# atmel.net
KiCad netlist of a schematic drawn in Altium Designer
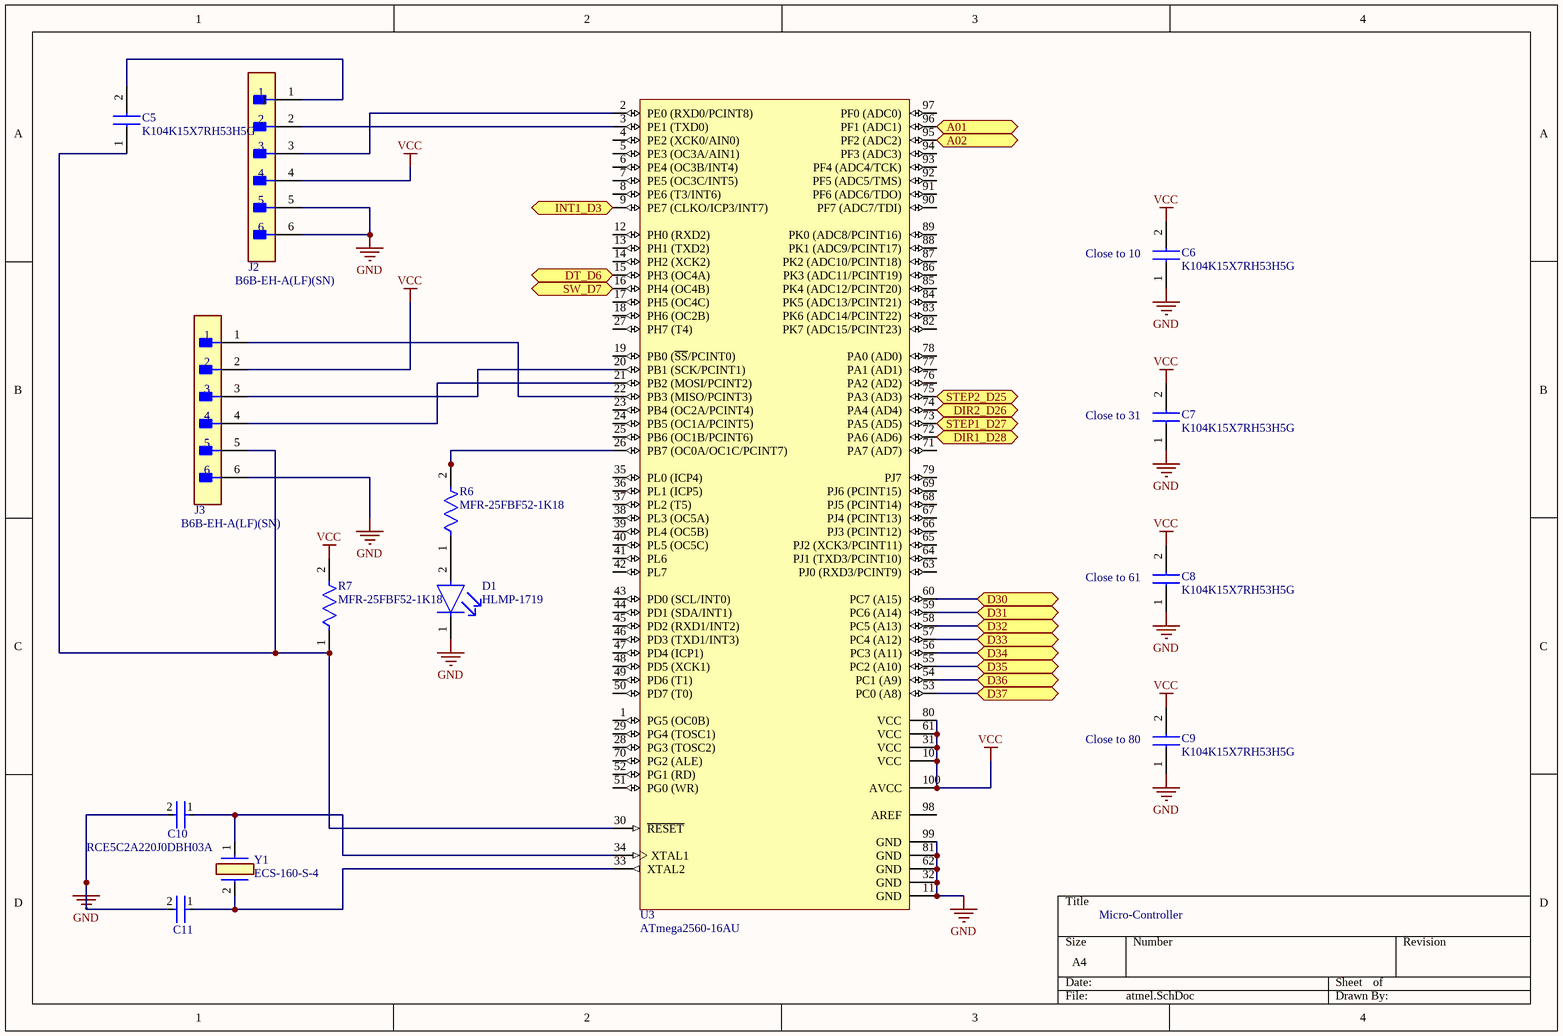
[diagram p0: atmel.SchDoc]

(export (version "E")
  (design (tool "Eeschema 10.0.6"))
  (components
    (comp (ref "C5")
      (value "K104K15X7RH53H5G")
      (footprint "SamacSys:K104K15X7RH53H5G")
      (description "Capacitor")
      (fields (field (name "MOUSER PART NUMBER") "594-K104K15X7RH53H5G"))
      (libsource (lib "*") (part "K104K15X7RH53H5G"))
    )
    (comp (ref "C6")
      (value "K104K15X7RH53H5G")
      (footprint "SamacSys:K104K15X7RH53H5G")
      (description "Capacitor")
      (fields (field (name "MOUSER PART NUMBER") "594-K104K15X7RH53H5G"))
      (libsource (lib "*") (part "K104K15X7RH53H5G"))
    )
    (comp (ref "C7")
      (value "K104K15X7RH53H5G")
      (footprint "SamacSys:K104K15X7RH53H5G")
      (description "Capacitor")
      (fields (field (name "MOUSER PART NUMBER") "594-K104K15X7RH53H5G"))
      (libsource (lib "*") (part "K104K15X7RH53H5G"))
    )
    (comp (ref "C8")
      (value "K104K15X7RH53H5G")
      (footprint "SamacSys:K104K15X7RH53H5G")
      (description "Capacitor")
      (fields (field (name "MOUSER PART NUMBER") "594-K104K15X7RH53H5G"))
      (libsource (lib "*") (part "K104K15X7RH53H5G"))
    )
    (comp (ref "C9")
      (value "K104K15X7RH53H5G")
      (footprint "SamacSys:K104K15X7RH53H5G")
      (description "Capacitor")
      (fields (field (name "MOUSER PART NUMBER") "594-K104K15X7RH53H5G"))
      (libsource (lib "*") (part "K104K15X7RH53H5G"))
    )
    (comp (ref "C10")
      (value "RCE5C2A220J0DBH03A")
      (footprint "FP-RCE0DB-MFG")
      (description "Cap Ceramic 22pF 100V C0G ±5% Radial 2.5mm +125°C Ammo Pack")
      (fields (field (name "VOLTAGE") "100V") (field (name "TOLERANCE") "5%"))
      (libsource (lib "Altium Content Vault") (part "b4654b650e69147ec39a6b967a45e02"))
    )
    (comp (ref "C11")
      (value "RCE5C2A220J0DBH03A")
      (footprint "FP-RCE0DB-MFG")
      (description "Cap Ceramic 22pF 100V C0G ±5% Radial 2.5mm +125°C Ammo Pack")
      (fields (field (name "VOLTAGE") "100V") (field (name "TOLERANCE") "5%"))
      (libsource (lib "Altium Content Vault") (part "b4654b650e69147ec39a6b967a45e02"))
    )
    (comp (ref "D1")
      (value "HLMP-1719")
      (footprint "FP-HLMP-1719-MFG")
      (description "LED YELLOW DIFFUSED T-1 T/H")
      (fields
        (field (name "MANUFACTURER") "Broadcom")
        (field (name "OCTOPART") "https://octopart.com/hlmp-1719-broadcom-71130405")
      )
      (libsource (lib "Altium Content Vault") (part "8706943c75ba83719d021d2fdc84c58"))
    )
    (comp (ref "J2")
      (value "B6B-EH-A(LF)(SN)")
      (footprint "FP-B6B-EH-A_LF_SN-MFG")
      (description "CONN HEADER VERT 6POS 2.5MM")
      (libsource (lib "") (part "f2cb566baf1c37ab5a3b8e90bbeafd6_1"))
    )
    (comp (ref "J3")
      (value "B6B-EH-A(LF)(SN)")
      (footprint "FP-B6B-EH-A_LF_SN-MFG")
      (description "CONN HEADER VERT 6POS 2.5MM")
      (libsource (lib "Altium Content Vault") (part "f2cb566baf1c37ab5a3b8e90bbeafd6"))
    )
    (comp (ref "R6")
      (value "MFR-25FBF52-1K18")
      (footprint "FP-MFR-25-MFG")
      (description "RES 1.18K OHM 1/4W 1% AXIAL")
      (fields (field (name "MANUFACTURER") "Yageo") (field (name "TOLERANCE") "1%"))
      (libsource (lib "Altium Content Vault") (part "1029c3af85768c4190bb7ad29bc67b5"))
    )
    (comp (ref "R7")
      (value "MFR-25FBF52-1K18")
      (footprint "FP-MFR-25-MFG")
      (description "RES 1.18K OHM 1/4W 1% AXIAL")
      (fields (field (name "MANUFACTURER") "Yageo") (field (name "TOLERANCE") "1%"))
      (libsource (lib "Altium Content Vault") (part "1029c3af85768c4190bb7ad29bc67b5"))
    )
    (comp (ref "U3")
      (value "ATmega2560-16AU")
      (footprint "100A_M")
      (libsource (lib "Altium Content Vault") (part "MC-8B-ATM640-SQ100"))
    )
    (comp (ref "Y1")
      (value "ECS-160-S-4")
      (footprint "SamacSys:ECS160S4")
      (description "Crystal or Oscillator")
      (fields (field (name "MOUSER PART NUMBER") "520-HCU1600-S"))
      (libsource (lib "*") (part "ECS-160-S-4"))
    )
  )
  (nets
    (net (code "1") (name "/A01") (class "Default")
      (node (ref "U3") (pin "96") (pinfunction "PF1_(ADC1)_96") (pintype "bidirectional"))
    )
    (net (code "2") (name "/A02") (class "Default")
      (node (ref "U3") (pin "95") (pinfunction "PF2_(ADC2)_95") (pintype "bidirectional"))
    )
    (net (code "3") (name "/D30") (class "Default")
      (node (ref "U3") (pin "60") (pinfunction "PC7_(A15)_60") (pintype "bidirectional"))
    )
    (net (code "4") (name "/D31") (class "Default")
      (node (ref "U3") (pin "59") (pinfunction "PC6_(A14)_59") (pintype "bidirectional"))
    )
    (net (code "5") (name "/D32") (class "Default")
      (node (ref "U3") (pin "58") (pinfunction "PC5_(A13)_58") (pintype "bidirectional"))
    )
    (net (code "6") (name "/D33") (class "Default")
      (node (ref "U3") (pin "57") (pinfunction "PC4_(A12)_57") (pintype "bidirectional"))
    )
    (net (code "7") (name "/D34") (class "Default")
      (node (ref "U3") (pin "56") (pinfunction "PC3_(A11)_56") (pintype "bidirectional"))
    )
    (net (code "8") (name "/D35") (class "Default")
      (node (ref "U3") (pin "55") (pinfunction "PC2_(A10)_55") (pintype "bidirectional"))
    )
    (net (code "9") (name "/D36") (class "Default")
      (node (ref "U3") (pin "54") (pinfunction "PC1_(A9)_54") (pintype "bidirectional"))
    )
    (net (code "10") (name "/D37") (class "Default")
      (node (ref "U3") (pin "53") (pinfunction "PC0_(A8)_53") (pintype "bidirectional"))
    )
    (net (code "11") (name "/DIR1_D28") (class "Default")
      (node (ref "U3") (pin "72") (pinfunction "PA6_(AD6)_72") (pintype "bidirectional"))
    )
    (net (code "12") (name "/DIR2_D26") (class "Default")
      (node (ref "U3") (pin "74") (pinfunction "PA4_(AD4)_74") (pintype "bidirectional"))
    )
    (net (code "13") (name "/DT_D6") (class "Default")
      (node (ref "U3") (pin "15") (pinfunction "PH3_(OC4A)_15") (pintype "bidirectional"))
    )
    (net (code "14") (name "/INT1_D3") (class "Default")
      (node (ref "U3") (pin "9") (pinfunction "PE7_(CLKO/ICP3/INT7)_9") (pintype "bidirectional"))
    )
    (net (code "15") (name "/STEP1_D27") (class "Default")
      (node (ref "U3") (pin "73") (pinfunction "PA5_(AD5)_73") (pintype "bidirectional"))
    )
    (net (code "16") (name "/STEP2_D25") (class "Default")
      (node (ref "U3") (pin "75") (pinfunction "PA3_(AD3)_75") (pintype "bidirectional"))
    )
    (net (code "17") (name "/SW_D7") (class "Default")
      (node (ref "U3") (pin "16") (pinfunction "PH4_(OC4B)_16") (pintype "bidirectional"))
    )
    (net (code "18") (name "GND") (class "Default")
      (node (ref "C10") (pin "2") (pinfunction "2_2") (pintype "passive"))
      (node (ref "C11") (pin "2") (pinfunction "2_2") (pintype "passive"))
      (node (ref "C6") (pin "1") (pinfunction "1_1") (pintype "passive"))
      (node (ref "C7") (pin "1") (pinfunction "1_1") (pintype "passive"))
      (node (ref "C8") (pin "1") (pinfunction "1_1") (pintype "passive"))
      (node (ref "C9") (pin "1") (pinfunction "1_1") (pintype "passive"))
      (node (ref "D1") (pin "1") (pinfunction "C_1") (pintype "passive"))
      (node (ref "J2") (pin "5") (pinfunction "5_5") (pintype "passive"))
      (node (ref "J2") (pin "6") (pinfunction "6_6") (pintype "passive"))
      (node (ref "J3") (pin "6") (pinfunction "6_6") (pintype "passive"))
      (node (ref "U3") (pin "11") (pinfunction "GND_11") (pintype "power_in"))
      (node (ref "U3") (pin "32") (pinfunction "GND_32") (pintype "power_in"))
      (node (ref "U3") (pin "62") (pinfunction "GND_62") (pintype "power_in"))
      (node (ref "U3") (pin "81") (pinfunction "GND_81") (pintype "power_in"))
      (node (ref "U3") (pin "99") (pinfunction "GND_99") (pintype "power_in"))
    )
    (net (code "19") (name "Net-(C5-Pad2)") (class "Default")
      (node (ref "C5") (pin "2") (pinfunction "2_2") (pintype "passive"))
      (node (ref "J2") (pin "1") (pinfunction "1_1") (pintype "passive"))
    )
    (net (code "20") (name "Net-(D1-A)") (class "Default")
      (node (ref "D1") (pin "2") (pinfunction "A_2") (pintype "passive"))
      (node (ref "R6") (pin "1") (pinfunction "1_1") (pintype "passive"))
    )
    (net (code "21") (name "Net-(U3-PB1_(SCK{slash}PCINT1))") (class "Default")
      (node (ref "J3") (pin "3") (pinfunction "3_3") (pintype "passive"))
      (node (ref "U3") (pin "20") (pinfunction "PB1_(SCK/PCINT1)_20") (pintype "bidirectional"))
    )
    (net (code "22") (name "Net-(U3-PB2_(MOSI{slash}PCINT2))") (class "Default")
      (node (ref "J3") (pin "4") (pinfunction "4_4") (pintype "passive"))
      (node (ref "U3") (pin "21") (pinfunction "PB2_(MOSI/PCINT2)_21") (pintype "bidirectional"))
    )
    (net (code "23") (name "Net-(U3-PB3_(MISO{slash}PCINT3))") (class "Default")
      (node (ref "J3") (pin "1") (pinfunction "1_1") (pintype "passive"))
      (node (ref "U3") (pin "22") (pinfunction "PB3_(MISO/PCINT3)_22") (pintype "bidirectional"))
    )
    (net (code "24") (name "Net-(U3-PB7_(OC0A{slash}OC1C{slash}PCINT7))") (class "Default")
      (node (ref "R6") (pin "2") (pinfunction "2_2") (pintype "passive"))
      (node (ref "U3") (pin "26") (pinfunction "PB7_(OC0A/OC1C/PCINT7)_26") (pintype "bidirectional"))
    )
    (net (code "25") (name "Net-(U3-PE0_(RXD0{slash}PCINT8))") (class "Default")
      (node (ref "J2") (pin "3") (pinfunction "3_3") (pintype "passive"))
      (node (ref "U3") (pin "2") (pinfunction "PE0_(RXD0/PCINT8)_2") (pintype "bidirectional"))
    )
    (net (code "26") (name "Net-(U3-PE1_(TXD0))") (class "Default")
      (node (ref "J2") (pin "2") (pinfunction "2_2") (pintype "passive"))
      (node (ref "U3") (pin "3") (pinfunction "PE1_(TXD0)_3") (pintype "bidirectional"))
    )
    (net (code "27") (name "Net-(U3-XTAL1)") (class "Default")
      (node (ref "C10") (pin "1") (pinfunction "1_1") (pintype "passive"))
      (node (ref "U3") (pin "34") (pinfunction "XTAL1_34") (pintype "input"))
      (node (ref "Y1") (pin "1") (pinfunction "1_1") (pintype "passive"))
    )
    (net (code "28") (name "Net-(U3-XTAL2)") (class "Default")
      (node (ref "C11") (pin "1") (pinfunction "1_1") (pintype "passive"))
      (node (ref "U3") (pin "33") (pinfunction "XTAL2_33") (pintype "output"))
      (node (ref "Y1") (pin "2") (pinfunction "2_2") (pintype "passive"))
    )
    (net (code "29") (name "Net-(U3-~{RESET})") (class "Default")
      (node (ref "C5") (pin "1") (pinfunction "1_1") (pintype "passive"))
      (node (ref "J3") (pin "5") (pinfunction "5_5") (pintype "passive"))
      (node (ref "R7") (pin "1") (pinfunction "1_1") (pintype "passive"))
      (node (ref "U3") (pin "30") (pinfunction "~{RESET}_30") (pintype "input"))
    )
    (net (code "30") (name "VCC") (class "Default")
      (node (ref "C6") (pin "2") (pinfunction "2_2") (pintype "passive"))
      (node (ref "C7") (pin "2") (pinfunction "2_2") (pintype "passive"))
      (node (ref "C8") (pin "2") (pinfunction "2_2") (pintype "passive"))
      (node (ref "C9") (pin "2") (pinfunction "2_2") (pintype "passive"))
      (node (ref "J2") (pin "4") (pinfunction "4_4") (pintype "passive"))
      (node (ref "J3") (pin "2") (pinfunction "2_2") (pintype "passive"))
      (node (ref "R7") (pin "2") (pinfunction "2_2") (pintype "passive"))
      (node (ref "U3") (pin "10") (pinfunction "VCC_10") (pintype "power_in"))
      (node (ref "U3") (pin "100") (pinfunction "AVCC_100") (pintype "power_in"))
      (node (ref "U3") (pin "31") (pinfunction "VCC_31") (pintype "power_in"))
      (node (ref "U3") (pin "61") (pinfunction "VCC_61") (pintype "power_in"))
      (node (ref "U3") (pin "80") (pinfunction "VCC_80") (pintype "power_in"))
    )
    (net (code "31") (name "unconnected-(U3-AREF-Pad98)") (class "Default")
      (node (ref "U3") (pin "98") (pinfunction "AREF_98") (pintype "power_in"))
    )
    (net (code "32") (name "unconnected-(U3-PA0_(AD0)-Pad78)") (class "Default")
      (node (ref "U3") (pin "78") (pinfunction "PA0_(AD0)_78") (pintype "bidirectional"))
    )
    (net (code "33") (name "unconnected-(U3-PA1_(AD1)-Pad77)") (class "Default")
      (node (ref "U3") (pin "77") (pinfunction "PA1_(AD1)_77") (pintype "bidirectional"))
    )
    (net (code "34") (name "unconnected-(U3-PA2_(AD2)-Pad76)") (class "Default")
      (node (ref "U3") (pin "76") (pinfunction "PA2_(AD2)_76") (pintype "bidirectional"))
    )
    (net (code "35") (name "unconnected-(U3-PA7_(AD7)-Pad71)") (class "Default")
      (node (ref "U3") (pin "71") (pinfunction "PA7_(AD7)_71") (pintype "bidirectional"))
    )
    (net (code "36") (name "unconnected-(U3-PB0_(~{SS}{slash}PCINT0)-Pad19)") (class "Default")
      (node (ref "U3") (pin "19") (pinfunction "PB0_(~{SS}/PCINT0)_19") (pintype "bidirectional"))
    )
    (net (code "37") (name "unconnected-(U3-PB4_(OC2A{slash}PCINT4)-Pad23)") (class "Default")
      (node (ref "U3") (pin "23") (pinfunction "PB4_(OC2A/PCINT4)_23") (pintype "bidirectional"))
    )
    (net (code "38") (name "unconnected-(U3-PB5_(OC1A{slash}PCINT5)-Pad24)") (class "Default")
      (node (ref "U3") (pin "24") (pinfunction "PB5_(OC1A/PCINT5)_24") (pintype "bidirectional"))
    )
    (net (code "39") (name "unconnected-(U3-PB6_(OC1B{slash}PCINT6)-Pad25)") (class "Default")
      (node (ref "U3") (pin "25") (pinfunction "PB6_(OC1B/PCINT6)_25") (pintype "bidirectional"))
    )
    (net (code "40") (name "unconnected-(U3-PD0_(SCL{slash}INT0)-Pad43)") (class "Default")
      (node (ref "U3") (pin "43") (pinfunction "PD0_(SCL/INT0)_43") (pintype "bidirectional"))
    )
    (net (code "41") (name "unconnected-(U3-PD1_(SDA{slash}INT1)-Pad44)") (class "Default")
      (node (ref "U3") (pin "44") (pinfunction "PD1_(SDA/INT1)_44") (pintype "bidirectional"))
    )
    (net (code "42") (name "unconnected-(U3-PD2_(RXD1{slash}INT2)-Pad45)") (class "Default")
      (node (ref "U3") (pin "45") (pinfunction "PD2_(RXD1/INT2)_45") (pintype "bidirectional"))
    )
    (net (code "43") (name "unconnected-(U3-PD3_(TXD1{slash}INT3)-Pad46)") (class "Default")
      (node (ref "U3") (pin "46") (pinfunction "PD3_(TXD1/INT3)_46") (pintype "bidirectional"))
    )
    (net (code "44") (name "unconnected-(U3-PD4_(ICP1)-Pad47)") (class "Default")
      (node (ref "U3") (pin "47") (pinfunction "PD4_(ICP1)_47") (pintype "bidirectional"))
    )
    (net (code "45") (name "unconnected-(U3-PD5_(XCK1)-Pad48)") (class "Default")
      (node (ref "U3") (pin "48") (pinfunction "PD5_(XCK1)_48") (pintype "bidirectional"))
    )
    (net (code "46") (name "unconnected-(U3-PD6_(T1)-Pad49)") (class "Default")
      (node (ref "U3") (pin "49") (pinfunction "PD6_(T1)_49") (pintype "bidirectional"))
    )
    (net (code "47") (name "unconnected-(U3-PD7_(T0)-Pad50)") (class "Default")
      (node (ref "U3") (pin "50") (pinfunction "PD7_(T0)_50") (pintype "bidirectional"))
    )
    (net (code "48") (name "unconnected-(U3-PE2_(XCK0{slash}AIN0)-Pad4)") (class "Default")
      (node (ref "U3") (pin "4") (pinfunction "PE2_(XCK0/AIN0)_4") (pintype "bidirectional"))
    )
    (net (code "49") (name "unconnected-(U3-PE3_(OC3A{slash}AIN1)-Pad5)") (class "Default")
      (node (ref "U3") (pin "5") (pinfunction "PE3_(OC3A/AIN1)_5") (pintype "bidirectional"))
    )
    (net (code "50") (name "unconnected-(U3-PE4_(OC3B{slash}INT4)-Pad6)") (class "Default")
      (node (ref "U3") (pin "6") (pinfunction "PE4_(OC3B/INT4)_6") (pintype "bidirectional"))
    )
    (net (code "51") (name "unconnected-(U3-PE5_(OC3C{slash}INT5)-Pad7)") (class "Default")
      (node (ref "U3") (pin "7") (pinfunction "PE5_(OC3C/INT5)_7") (pintype "bidirectional"))
    )
    (net (code "52") (name "unconnected-(U3-PE6_(T3{slash}INT6)-Pad8)") (class "Default")
      (node (ref "U3") (pin "8") (pinfunction "PE6_(T3/INT6)_8") (pintype "bidirectional"))
    )
    (net (code "53") (name "unconnected-(U3-PF0_(ADC0)-Pad97)") (class "Default")
      (node (ref "U3") (pin "97") (pinfunction "PF0_(ADC0)_97") (pintype "bidirectional"))
    )
    (net (code "54") (name "unconnected-(U3-PF3_(ADC3)-Pad94)") (class "Default")
      (node (ref "U3") (pin "94") (pinfunction "PF3_(ADC3)_94") (pintype "bidirectional"))
    )
    (net (code "55") (name "unconnected-(U3-PF4_(ADC4{slash}TCK)-Pad93)") (class "Default")
      (node (ref "U3") (pin "93") (pinfunction "PF4_(ADC4/TCK)_93") (pintype "bidirectional"))
    )
    (net (code "56") (name "unconnected-(U3-PF5_(ADC5{slash}TMS)-Pad92)") (class "Default")
      (node (ref "U3") (pin "92") (pinfunction "PF5_(ADC5/TMS)_92") (pintype "bidirectional"))
    )
    (net (code "57") (name "unconnected-(U3-PF6_(ADC6{slash}TDO)-Pad91)") (class "Default")
      (node (ref "U3") (pin "91") (pinfunction "PF6_(ADC6/TDO)_91") (pintype "bidirectional"))
    )
    (net (code "58") (name "unconnected-(U3-PF7_(ADC7{slash}TDI)-Pad90)") (class "Default")
      (node (ref "U3") (pin "90") (pinfunction "PF7_(ADC7/TDI)_90") (pintype "bidirectional"))
    )
    (net (code "59") (name "unconnected-(U3-PG0_(WR)-Pad51)") (class "Default")
      (node (ref "U3") (pin "51") (pinfunction "PG0_(WR)_51") (pintype "bidirectional"))
    )
    (net (code "60") (name "unconnected-(U3-PG1_(RD)-Pad52)") (class "Default")
      (node (ref "U3") (pin "52") (pinfunction "PG1_(RD)_52") (pintype "bidirectional"))
    )
    (net (code "61") (name "unconnected-(U3-PG2_(ALE)-Pad70)") (class "Default")
      (node (ref "U3") (pin "70") (pinfunction "PG2_(ALE)_70") (pintype "bidirectional"))
    )
    (net (code "62") (name "unconnected-(U3-PG3_(TOSC2)-Pad28)") (class "Default")
      (node (ref "U3") (pin "28") (pinfunction "PG3_(TOSC2)_28") (pintype "bidirectional"))
    )
    (net (code "63") (name "unconnected-(U3-PG4_(TOSC1)-Pad29)") (class "Default")
      (node (ref "U3") (pin "29") (pinfunction "PG4_(TOSC1)_29") (pintype "bidirectional"))
    )
    (net (code "64") (name "unconnected-(U3-PG5_(OC0B)-Pad1)") (class "Default")
      (node (ref "U3") (pin "1") (pinfunction "PG5_(OC0B)_1") (pintype "bidirectional"))
    )
    (net (code "65") (name "unconnected-(U3-PH0_(RXD2)-Pad12)") (class "Default")
      (node (ref "U3") (pin "12") (pinfunction "PH0_(RXD2)_12") (pintype "bidirectional"))
    )
    (net (code "66") (name "unconnected-(U3-PH1_(TXD2)-Pad13)") (class "Default")
      (node (ref "U3") (pin "13") (pinfunction "PH1_(TXD2)_13") (pintype "bidirectional"))
    )
    (net (code "67") (name "unconnected-(U3-PH2_(XCK2)-Pad14)") (class "Default")
      (node (ref "U3") (pin "14") (pinfunction "PH2_(XCK2)_14") (pintype "bidirectional"))
    )
    (net (code "68") (name "unconnected-(U3-PH5_(OC4C)-Pad17)") (class "Default")
      (node (ref "U3") (pin "17") (pinfunction "PH5_(OC4C)_17") (pintype "bidirectional"))
    )
    (net (code "69") (name "unconnected-(U3-PH6_(OC2B)-Pad18)") (class "Default")
      (node (ref "U3") (pin "18") (pinfunction "PH6_(OC2B)_18") (pintype "bidirectional"))
    )
    (net (code "70") (name "unconnected-(U3-PH7_(T4)-Pad27)") (class "Default")
      (node (ref "U3") (pin "27") (pinfunction "PH7_(T4)_27") (pintype "bidirectional"))
    )
    (net (code "71") (name "unconnected-(U3-PJ0_(RXD3{slash}PCINT9)-Pad63)") (class "Default")
      (node (ref "U3") (pin "63") (pinfunction "PJ0_(RXD3/PCINT9)_63") (pintype "bidirectional"))
    )
    (net (code "72") (name "unconnected-(U3-PJ1_(TXD3{slash}PCINT10)-Pad64)") (class "Default")
      (node (ref "U3") (pin "64") (pinfunction "PJ1_(TXD3/PCINT10)_64") (pintype "bidirectional"))
    )
    (net (code "73") (name "unconnected-(U3-PJ2_(XCK3{slash}PCINT11)-Pad65)") (class "Default")
      (node (ref "U3") (pin "65") (pinfunction "PJ2_(XCK3/PCINT11)_65") (pintype "bidirectional"))
    )
    (net (code "74") (name "unconnected-(U3-PJ3_(PCINT12)-Pad66)") (class "Default")
      (node (ref "U3") (pin "66") (pinfunction "PJ3_(PCINT12)_66") (pintype "bidirectional"))
    )
    (net (code "75") (name "unconnected-(U3-PJ4_(PCINT13)-Pad67)") (class "Default")
      (node (ref "U3") (pin "67") (pinfunction "PJ4_(PCINT13)_67") (pintype "bidirectional"))
    )
    (net (code "76") (name "unconnected-(U3-PJ5_(PCINT14)-Pad68)") (class "Default")
      (node (ref "U3") (pin "68") (pinfunction "PJ5_(PCINT14)_68") (pintype "bidirectional"))
    )
    (net (code "77") (name "unconnected-(U3-PJ6_(PCINT15)-Pad69)") (class "Default")
      (node (ref "U3") (pin "69") (pinfunction "PJ6_(PCINT15)_69") (pintype "bidirectional"))
    )
    (net (code "78") (name "unconnected-(U3-PJ7-Pad79)") (class "Default")
      (node (ref "U3") (pin "79") (pinfunction "PJ7_79") (pintype "bidirectional"))
    )
    (net (code "79") (name "unconnected-(U3-PK0_(ADC8{slash}PCINT16)-Pad89)") (class "Default")
      (node (ref "U3") (pin "89") (pinfunction "PK0_(ADC8/PCINT16)_89") (pintype "bidirectional"))
    )
    (net (code "80") (name "unconnected-(U3-PK1_(ADC9{slash}PCINT17)-Pad88)") (class "Default")
      (node (ref "U3") (pin "88") (pinfunction "PK1_(ADC9/PCINT17)_88") (pintype "bidirectional"))
    )
    (net (code "81") (name "unconnected-(U3-PK2_(ADC10{slash}PCINT18)-Pad87)") (class "Default")
      (node (ref "U3") (pin "87") (pinfunction "PK2_(ADC10/PCINT18)_87") (pintype "bidirectional"))
    )
    (net (code "82") (name "unconnected-(U3-PK3_(ADC11{slash}PCINT19)-Pad86)") (class "Default")
      (node (ref "U3") (pin "86") (pinfunction "PK3_(ADC11/PCINT19)_86") (pintype "bidirectional"))
    )
    (net (code "83") (name "unconnected-(U3-PK4_(ADC12{slash}PCINT20)-Pad85)") (class "Default")
      (node (ref "U3") (pin "85") (pinfunction "PK4_(ADC12/PCINT20)_85") (pintype "bidirectional"))
    )
    (net (code "84") (name "unconnected-(U3-PK5_(ADC13{slash}PCINT21)-Pad84)") (class "Default")
      (node (ref "U3") (pin "84") (pinfunction "PK5_(ADC13/PCINT21)_84") (pintype "bidirectional"))
    )
    (net (code "85") (name "unconnected-(U3-PK6_(ADC14{slash}PCINT22)-Pad83)") (class "Default")
      (node (ref "U3") (pin "83") (pinfunction "PK6_(ADC14/PCINT22)_83") (pintype "bidirectional"))
    )
    (net (code "86") (name "unconnected-(U3-PK7_(ADC15{slash}PCINT23)-Pad82)") (class "Default")
      (node (ref "U3") (pin "82") (pinfunction "PK7_(ADC15/PCINT23)_82") (pintype "bidirectional"))
    )
    (net (code "87") (name "unconnected-(U3-PL0_(ICP4)-Pad35)") (class "Default")
      (node (ref "U3") (pin "35") (pinfunction "PL0_(ICP4)_35") (pintype "bidirectional"))
    )
    (net (code "88") (name "unconnected-(U3-PL1_(ICP5)-Pad36)") (class "Default")
      (node (ref "U3") (pin "36") (pinfunction "PL1_(ICP5)_36") (pintype "bidirectional"))
    )
    (net (code "89") (name "unconnected-(U3-PL2_(T5)-Pad37)") (class "Default")
      (node (ref "U3") (pin "37") (pinfunction "PL2_(T5)_37") (pintype "bidirectional"))
    )
    (net (code "90") (name "unconnected-(U3-PL3_(OC5A)-Pad38)") (class "Default")
      (node (ref "U3") (pin "38") (pinfunction "PL3_(OC5A)_38") (pintype "bidirectional"))
    )
    (net (code "91") (name "unconnected-(U3-PL4_(OC5B)-Pad39)") (class "Default")
      (node (ref "U3") (pin "39") (pinfunction "PL4_(OC5B)_39") (pintype "bidirectional"))
    )
    (net (code "92") (name "unconnected-(U3-PL5_(OC5C)-Pad40)") (class "Default")
      (node (ref "U3") (pin "40") (pinfunction "PL5_(OC5C)_40") (pintype "bidirectional"))
    )
    (net (code "93") (name "unconnected-(U3-PL6-Pad41)") (class "Default")
      (node (ref "U3") (pin "41") (pinfunction "PL6_41") (pintype "bidirectional"))
    )
    (net (code "94") (name "unconnected-(U3-PL7-Pad42)") (class "Default")
      (node (ref "U3") (pin "42") (pinfunction "PL7_42") (pintype "bidirectional"))
    )
  )
)
